# MotorCell_noPow.net
KiCad netlist of a schematic drawn in Altium Designer
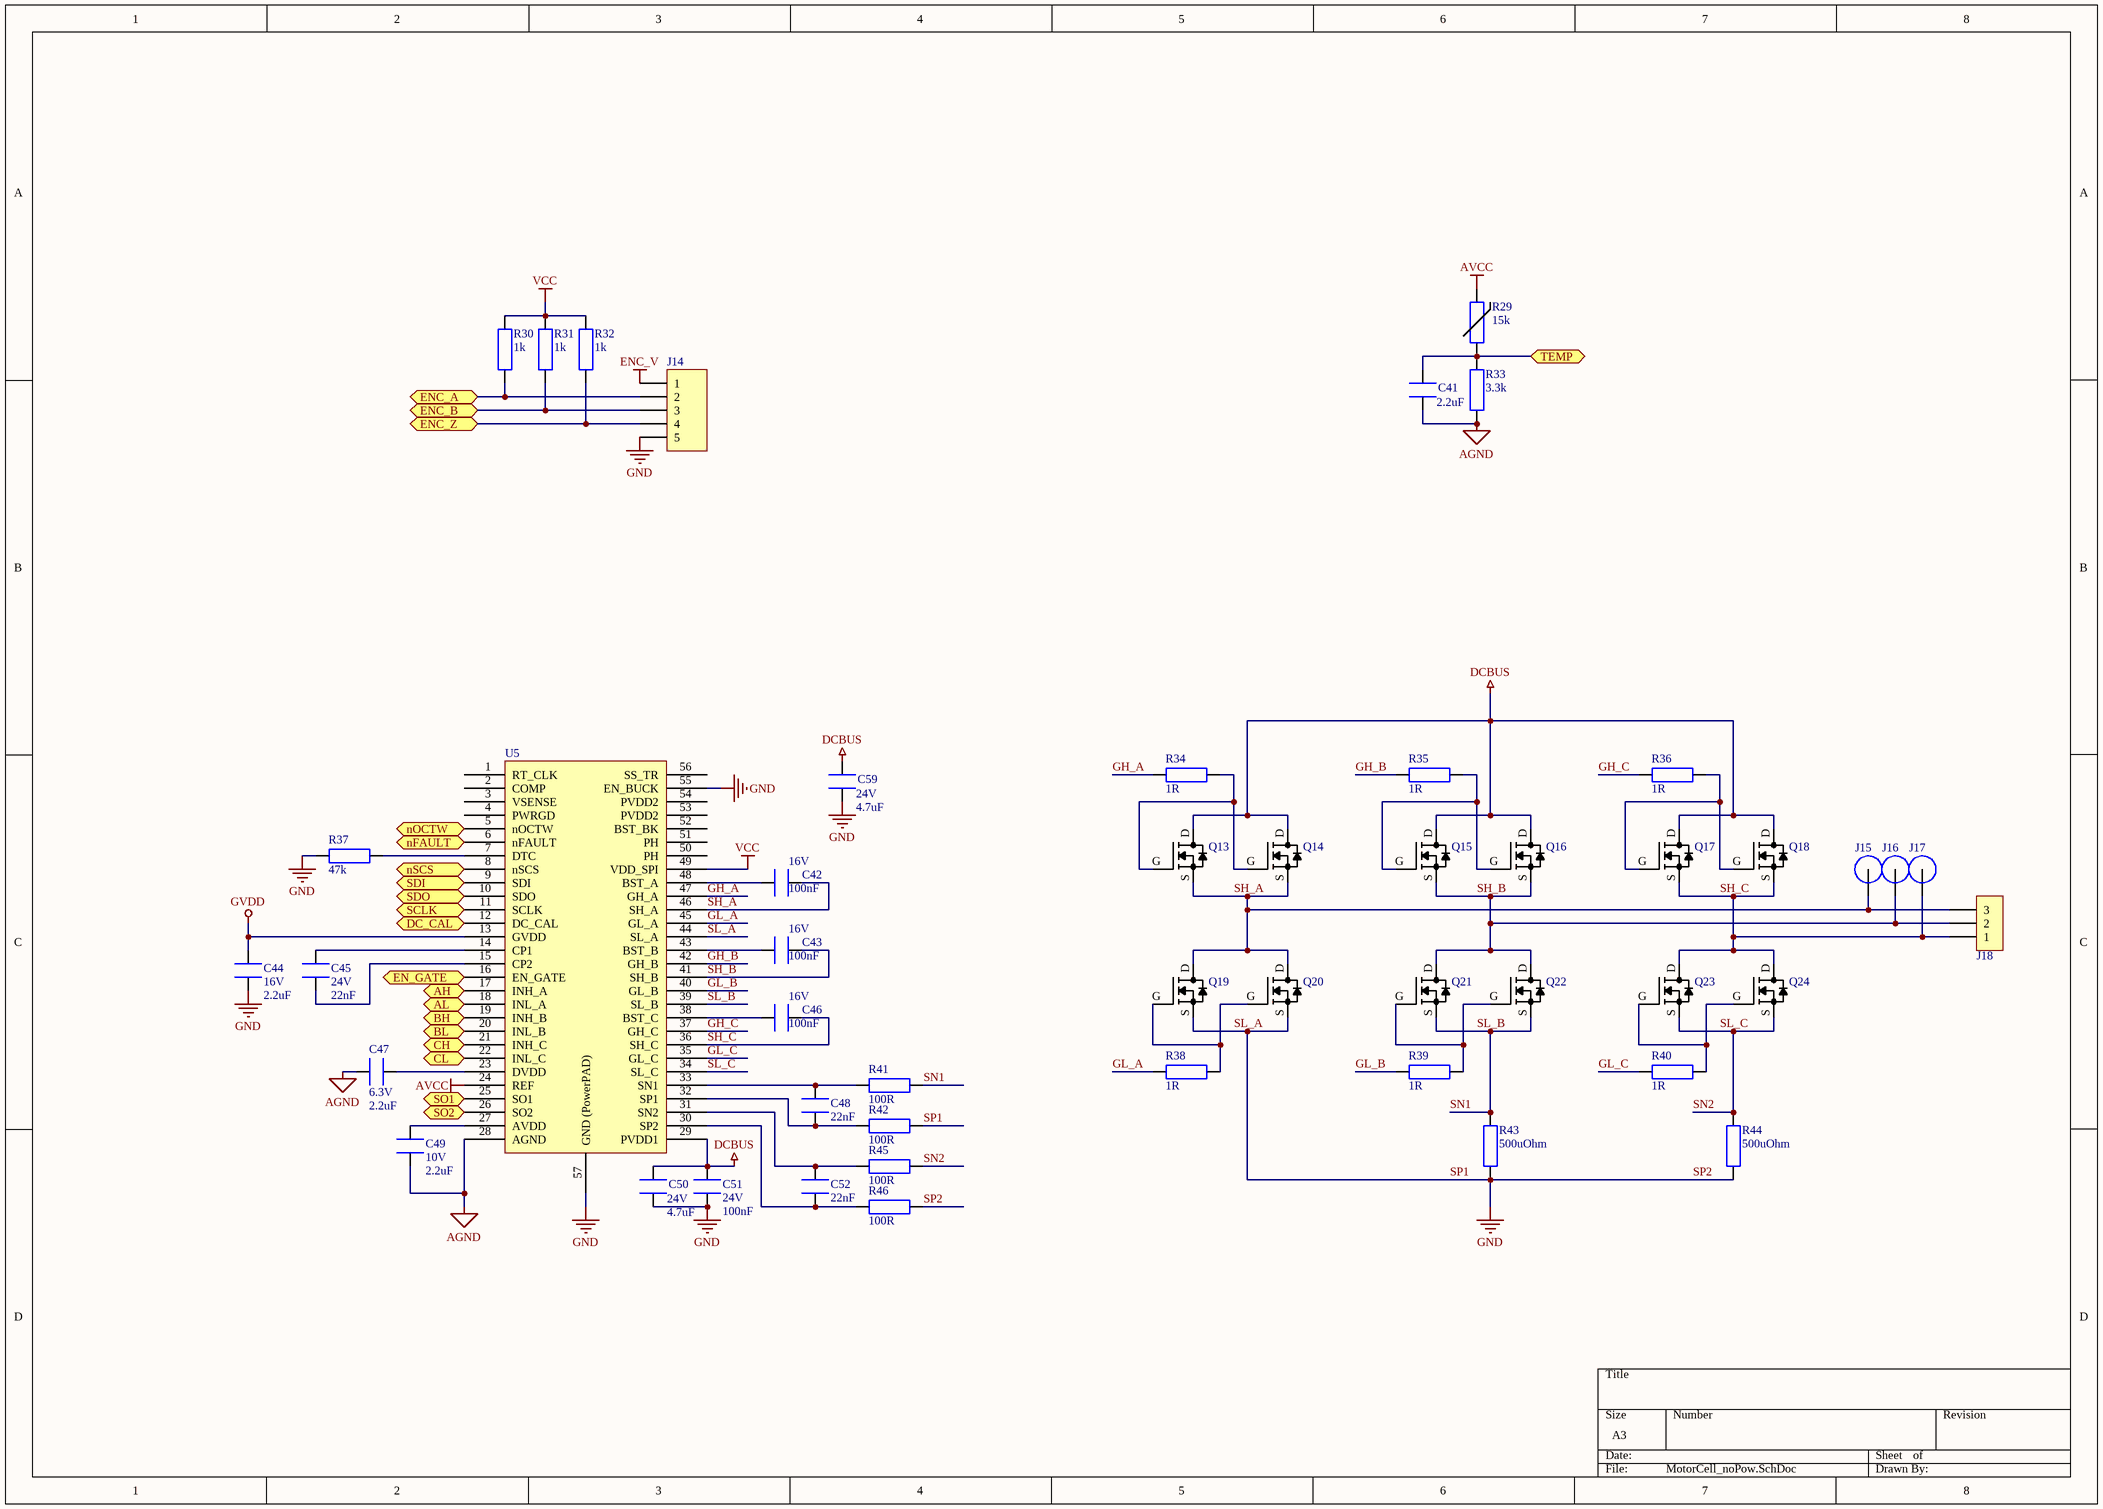
[diagram p0: MotorCell_noPow.SchDoc]

(export (version "E")
  (design (tool "Eeschema 10.0.6"))
  (components
    (comp (ref "C41")
      (value "2.2uF")
      (footprint "1608[0603]")
      (description "CAP General 0603")
      (libsource (lib "CustomComponents") (part "CAP_0603"))
    )
    (comp (ref "C42")
      (value "16V")
      (footprint "1608[0603]")
      (description "CAP General 0603")
      (fields (field (name "ALTIUM_VALUE") "100nF"))
      (libsource (lib "CustomComponents") (part "CAP_0603"))
    )
    (comp (ref "C43")
      (value "16V")
      (footprint "1608[0603]")
      (description "CAP General 0603")
      (fields (field (name "ALTIUM_VALUE") "100nF"))
      (libsource (lib "CustomComponents") (part "CAP_0603"))
    )
    (comp (ref "C44")
      (value "16V")
      (footprint "1608[0603]")
      (description "CAP General 0603")
      (fields (field (name "ALTIUM_VALUE") "2.2uF"))
      (libsource (lib "CustomComponents") (part "CAP_0603"))
    )
    (comp (ref "C45")
      (value "24V")
      (footprint "1608[0603]")
      (description "CAP General 0603")
      (fields (field (name "ALTIUM_VALUE") "22nF"))
      (libsource (lib "CustomComponents") (part "CAP_0603"))
    )
    (comp (ref "C46")
      (value "16V")
      (footprint "1608[0603]")
      (description "CAP General 0603")
      (fields (field (name "ALTIUM_VALUE") "100nF"))
      (libsource (lib "CustomComponents") (part "CAP_0603"))
    )
    (comp (ref "C47")
      (value "6.3V")
      (footprint "1608[0603]")
      (description "CAP General 0603")
      (fields (field (name "ALTIUM_VALUE") "2.2uF"))
      (libsource (lib "CustomComponents") (part "CAP_0603"))
    )
    (comp (ref "C48")
      (value "22nF")
      (footprint "1608[0603]")
      (description "CAP General 0603")
      (libsource (lib "CustomComponents") (part "CAP_0603"))
    )
    (comp (ref "C49")
      (value "10V")
      (footprint "1608[0603]")
      (description "CAP General 0603")
      (fields (field (name "ALTIUM_VALUE") "2.2uF"))
      (libsource (lib "CustomComponents") (part "CAP_0603"))
    )
    (comp (ref "C50")
      (value "24V")
      (footprint "CAPC2012X09N")
      (description "CAP CER 4.7UF 35V X5R 0805")
      (fields (field (name "ALTIUM_VALUE") "4.7uF"))
      (libsource (lib "CustomComponents") (part "GRM219R6YA475KA73D"))
    )
    (comp (ref "C51")
      (value "24V")
      (footprint "1608[0603]")
      (description "CAP General 0603")
      (fields (field (name "ALTIUM_VALUE") "100nF"))
      (libsource (lib "CustomComponents") (part "CAP_0603"))
    )
    (comp (ref "C52")
      (value "22nF")
      (footprint "1608[0603]")
      (description "CAP General 0603")
      (libsource (lib "CustomComponents") (part "CAP_0603"))
    )
    (comp (ref "C59")
      (value "24V")
      (footprint "CAPC2012X09N")
      (description "CAP CER 4.7UF 35V X5R 0805")
      (fields (field (name "ALTIUM_VALUE") "4.7uF"))
      (libsource (lib "CustomComponents") (part "GRM219R6YA475KA73D"))
    )
    (comp (ref "J14")
      (value "~")
      (footprint "HDR1X5")
      (description "Header, 5-Pin")
      (fields (field (name "PUBLISHER") "Altium Limited"))
      (libsource (lib "Miscellaneous Connectors") (part "Header 5"))
    )
    (comp (ref "J15")
      (value "~")
      (footprint "M3 Spade Hole")
      (description "M3 Spade Terminal")
      (libsource (lib "CustomComponents") (part "M3 Spade Terminal"))
    )
    (comp (ref "J16")
      (value "~")
      (footprint "M3 Spade Hole")
      (description "M3 Spade Terminal")
      (libsource (lib "CustomComponents") (part "M3 Spade Terminal"))
    )
    (comp (ref "J17")
      (value "~")
      (footprint "M3 Spade Hole")
      (description "M3 Spade Terminal")
      (libsource (lib "CustomComponents") (part "M3 Spade Terminal"))
    )
    (comp (ref "J18")
      (value "~")
      (footprint "MC000051")
      (description "TERMINAL BLOCK, WIRE TO BRD, 3POS, 10AWG")
      (libsource (lib "CustomComponents") (part "MC000051"))
    )
    (comp (ref "Q13")
      (value "~")
      (footprint "SO8FL")
      (description "MOSFET, N CH, 30V, 70A, SO-8 FL")
      (libsource (lib "CustomComponents") (part "NTMFS4937NT1G"))
    )
    (comp (ref "Q14")
      (value "~")
      (footprint "SO8FL_FILL")
      (description "MOSFET, N CH, 30V, 70A, SO-8 FL")
      (libsource (lib "CustomComponents") (part "NTMFS4937NT1G"))
    )
    (comp (ref "Q15")
      (value "~")
      (footprint "SO8FL")
      (description "MOSFET, N CH, 30V, 70A, SO-8 FL")
      (libsource (lib "CustomComponents") (part "NTMFS4937NT1G"))
    )
    (comp (ref "Q16")
      (value "~")
      (footprint "SO8FL_FILL")
      (description "MOSFET, N CH, 30V, 70A, SO-8 FL")
      (libsource (lib "CustomComponents") (part "NTMFS4937NT1G"))
    )
    (comp (ref "Q17")
      (value "~")
      (footprint "SO8FL")
      (description "MOSFET, N CH, 30V, 70A, SO-8 FL")
      (libsource (lib "CustomComponents") (part "NTMFS4937NT1G"))
    )
    (comp (ref "Q18")
      (value "~")
      (footprint "SO8FL_FILL")
      (description "MOSFET, N CH, 30V, 70A, SO-8 FL")
      (libsource (lib "CustomComponents") (part "NTMFS4937NT1G"))
    )
    (comp (ref "Q19")
      (value "~")
      (footprint "SO8FL")
      (description "MOSFET, N CH, 30V, 70A, SO-8 FL")
      (libsource (lib "CustomComponents") (part "NTMFS4937NT1G"))
    )
    (comp (ref "Q20")
      (value "~")
      (footprint "SO8FL")
      (description "MOSFET, N CH, 30V, 70A, SO-8 FL")
      (libsource (lib "CustomComponents") (part "NTMFS4937NT1G"))
    )
    (comp (ref "Q21")
      (value "~")
      (footprint "SO8FL")
      (description "MOSFET, N CH, 30V, 70A, SO-8 FL")
      (libsource (lib "CustomComponents") (part "NTMFS4937NT1G"))
    )
    (comp (ref "Q22")
      (value "~")
      (footprint "SO8FL")
      (description "MOSFET, N CH, 30V, 70A, SO-8 FL")
      (libsource (lib "CustomComponents") (part "NTMFS4937NT1G"))
    )
    (comp (ref "Q23")
      (value "~")
      (footprint "SO8FL")
      (description "MOSFET, N CH, 30V, 70A, SO-8 FL")
      (libsource (lib "CustomComponents") (part "NTMFS4937NT1G"))
    )
    (comp (ref "Q24")
      (value "~")
      (footprint "SO8FL")
      (description "MOSFET, N CH, 30V, 70A, SO-8 FL")
      (libsource (lib "CustomComponents") (part "NTMFS4937NT1G"))
    )
    (comp (ref "R29")
      (value "15k")
      (footprint "RESC1608X06L")
      (description "THERMISTOR, 15K, 5%, SMD, NTC")
      (libsource (lib "CustomComponents") (part "NTCS0603E3153JMT"))
    )
    (comp (ref "R30")
      (value "1k")
      (footprint "RESC1608X55N")
      (description "RES General 1% 0603")
      (libsource (lib "CustomComponents") (part "RES_0603"))
    )
    (comp (ref "R31")
      (value "1k")
      (footprint "RESC1608X55N")
      (description "RES General 1% 0603")
      (libsource (lib "CustomComponents") (part "RES_0603"))
    )
    (comp (ref "R32")
      (value "1k")
      (footprint "RESC1608X55N")
      (description "RES General 1% 0603")
      (libsource (lib "CustomComponents") (part "RES_0603"))
    )
    (comp (ref "R33")
      (value "3.3k")
      (footprint "RESC1608X55N")
      (description "RES General 1% 0603")
      (libsource (lib "CustomComponents") (part "RES_0603"))
    )
    (comp (ref "R34")
      (value "1R")
      (footprint "RESC1608X55N")
      (description "RES General 1% 0603")
      (libsource (lib "CustomComponents") (part "RES_0603"))
    )
    (comp (ref "R35")
      (value "1R")
      (footprint "RESC1608X55N")
      (description "RES General 1% 0603")
      (libsource (lib "CustomComponents") (part "RES_0603"))
    )
    (comp (ref "R36")
      (value "1R")
      (footprint "RESC1608X55N")
      (description "RES General 1% 0603")
      (libsource (lib "CustomComponents") (part "RES_0603"))
    )
    (comp (ref "R37")
      (value "47k")
      (footprint "RESC1608X55N")
      (description "RES General 1% 0603")
      (libsource (lib "CustomComponents") (part "RES_0603"))
    )
    (comp (ref "R38")
      (value "1R")
      (footprint "RESC1608X55N")
      (description "RES General 1% 0603")
      (libsource (lib "CustomComponents") (part "RES_0603"))
    )
    (comp (ref "R39")
      (value "1R")
      (footprint "RESC1608X55N")
      (description "RES General 1% 0603")
      (libsource (lib "CustomComponents") (part "RES_0603"))
    )
    (comp (ref "R40")
      (value "1R")
      (footprint "RESC1608X55N")
      (description "RES General 1% 0603")
      (libsource (lib "CustomComponents") (part "RES_0603"))
    )
    (comp (ref "R41")
      (value "100R")
      (footprint "RESC1608X55N")
      (description "RES General 1% 0603")
      (libsource (lib "CustomComponents") (part "RES_0603"))
    )
    (comp (ref "R42")
      (value "100R")
      (footprint "RESC1608X55N")
      (description "RES General 1% 0603")
      (libsource (lib "CustomComponents") (part "RES_0603"))
    )
    (comp (ref "R43")
      (value "500uOhm")
      (footprint "RESC6432X09N")
      (description "RES SMD 0.0005 OHM 1% 3W 2512")
      (libsource (lib "CustomComponents") (part "CSR2512C0R0005F"))
    )
    (comp (ref "R44")
      (value "500uOhm")
      (footprint "RESC6432X09N")
      (description "RES SMD 0.0005 OHM 1% 3W 2512")
      (libsource (lib "CustomComponents") (part "CSR2512C0R0005F"))
    )
    (comp (ref "R45")
      (value "100R")
      (footprint "RESC1608X55N")
      (description "RES General 1% 0603")
      (libsource (lib "CustomComponents") (part "RES_0603"))
    )
    (comp (ref "R46")
      (value "100R")
      (footprint "RESC1608X55N")
      (description "RES General 1% 0603")
      (libsource (lib "CustomComponents") (part "RES_0603"))
    )
    (comp (ref "U5")
      (value "~")
      (footprint "TSSOP50P810X120_HS-57N")
      (description "MOTOR DRIVER, 3PH, 56HTSSOP")
      (libsource (lib "CustomComponents") (part "DRV8301"))
    )
  )
  (nets
    (net (code "1") (name "/AH") (class "Default")
      (node (ref "U5") (pin "17") (pinfunction "INH_A_17") (pintype "passive"))
    )
    (net (code "2") (name "/AL") (class "Default")
      (node (ref "U5") (pin "18") (pinfunction "INL_A_18") (pintype "passive"))
    )
    (net (code "3") (name "/BH") (class "Default")
      (node (ref "U5") (pin "19") (pinfunction "INH_B_19") (pintype "passive"))
    )
    (net (code "4") (name "/BL") (class "Default")
      (node (ref "U5") (pin "20") (pinfunction "INL_B_20") (pintype "passive"))
    )
    (net (code "5") (name "/CH") (class "Default")
      (node (ref "U5") (pin "21") (pinfunction "INH_C_21") (pintype "passive"))
    )
    (net (code "6") (name "/CL") (class "Default")
      (node (ref "U5") (pin "22") (pinfunction "INL_C_22") (pintype "passive"))
    )
    (net (code "7") (name "/DC_CAL") (class "Default")
      (node (ref "U5") (pin "12") (pinfunction "DC_CAL_12") (pintype "passive"))
    )
    (net (code "8") (name "/ENC_A") (class "Default")
      (node (ref "J14") (pin "2") (pinfunction "2_2") (pintype "passive"))
      (node (ref "R30") (pin "2") (pinfunction "0_2") (pintype "passive"))
    )
    (net (code "9") (name "/ENC_B") (class "Default")
      (node (ref "J14") (pin "3") (pinfunction "3_3") (pintype "passive"))
      (node (ref "R31") (pin "2") (pinfunction "0_2") (pintype "passive"))
    )
    (net (code "10") (name "/ENC_Z") (class "Default")
      (node (ref "J14") (pin "4") (pinfunction "4_4") (pintype "passive"))
      (node (ref "R32") (pin "2") (pinfunction "0_2") (pintype "passive"))
    )
    (net (code "11") (name "/EN_GATE") (class "Default")
      (node (ref "U5") (pin "16") (pinfunction "EN_GATE_16") (pintype "passive"))
    )
    (net (code "12") (name "/GH_A") (class "Default")
      (node (ref "R34") (pin "1") (pinfunction "0_1") (pintype "passive"))
      (node (ref "U5") (pin "47") (pinfunction "GH_A_47") (pintype "passive"))
    )
    (net (code "13") (name "/GH_B") (class "Default")
      (node (ref "R35") (pin "1") (pinfunction "0_1") (pintype "passive"))
      (node (ref "U5") (pin "42") (pinfunction "GH_B_42") (pintype "passive"))
    )
    (net (code "14") (name "/GH_C") (class "Default")
      (node (ref "R36") (pin "1") (pinfunction "0_1") (pintype "passive"))
      (node (ref "U5") (pin "37") (pinfunction "GH_C_37") (pintype "passive"))
    )
    (net (code "15") (name "/GL_A") (class "Default")
      (node (ref "R38") (pin "1") (pinfunction "0_1") (pintype "passive"))
      (node (ref "U5") (pin "45") (pinfunction "GL_A_45") (pintype "passive"))
    )
    (net (code "16") (name "/GL_B") (class "Default")
      (node (ref "R39") (pin "1") (pinfunction "0_1") (pintype "passive"))
      (node (ref "U5") (pin "40") (pinfunction "GL_B_40") (pintype "passive"))
    )
    (net (code "17") (name "/GL_C") (class "Default")
      (node (ref "R40") (pin "1") (pinfunction "0_1") (pintype "passive"))
      (node (ref "U5") (pin "35") (pinfunction "GL_C_35") (pintype "passive"))
    )
    (net (code "18") (name "/SCLK") (class "Default")
      (node (ref "U5") (pin "11") (pinfunction "SCLK_11") (pintype "passive"))
    )
    (net (code "19") (name "/SDI") (class "Default")
      (node (ref "U5") (pin "9") (pinfunction "SDI_9") (pintype "passive"))
    )
    (net (code "20") (name "/SDO") (class "Default")
      (node (ref "U5") (pin "10") (pinfunction "SDO_10") (pintype "passive"))
    )
    (net (code "21") (name "/SH_A") (class "Default")
      (node (ref "C42") (pin "1") (pinfunction "1_1") (pintype "passive"))
      (node (ref "J15") (pin "1") (pinfunction "1_1") (pintype "passive"))
      (node (ref "J18") (pin "3") (pinfunction "3_3") (pintype "passive"))
      (node (ref "Q13") (pin "S") (pinfunction "S_S") (pintype "passive"))
      (node (ref "Q14") (pin "S") (pinfunction "S_S") (pintype "passive"))
      (node (ref "Q19") (pin "D") (pinfunction "D_D") (pintype "passive"))
      (node (ref "Q20") (pin "D") (pinfunction "D_D") (pintype "passive"))
      (node (ref "U5") (pin "46") (pinfunction "SH_A_46") (pintype "passive"))
    )
    (net (code "22") (name "/SH_B") (class "Default")
      (node (ref "C43") (pin "1") (pinfunction "1_1") (pintype "passive"))
      (node (ref "J16") (pin "1") (pinfunction "1_1") (pintype "passive"))
      (node (ref "J18") (pin "2") (pinfunction "2_2") (pintype "passive"))
      (node (ref "Q15") (pin "S") (pinfunction "S_S") (pintype "passive"))
      (node (ref "Q16") (pin "S") (pinfunction "S_S") (pintype "passive"))
      (node (ref "Q21") (pin "D") (pinfunction "D_D") (pintype "passive"))
      (node (ref "Q22") (pin "D") (pinfunction "D_D") (pintype "passive"))
      (node (ref "U5") (pin "41") (pinfunction "SH_B_41") (pintype "passive"))
    )
    (net (code "23") (name "/SH_C") (class "Default")
      (node (ref "C46") (pin "1") (pinfunction "1_1") (pintype "passive"))
      (node (ref "J17") (pin "1") (pinfunction "1_1") (pintype "passive"))
      (node (ref "J18") (pin "1") (pinfunction "1_1") (pintype "passive"))
      (node (ref "Q17") (pin "S") (pinfunction "S_S") (pintype "passive"))
      (node (ref "Q18") (pin "S") (pinfunction "S_S") (pintype "passive"))
      (node (ref "Q23") (pin "D") (pinfunction "D_D") (pintype "passive"))
      (node (ref "Q24") (pin "D") (pinfunction "D_D") (pintype "passive"))
      (node (ref "U5") (pin "36") (pinfunction "SH_C_36") (pintype "passive"))
    )
    (net (code "24") (name "/SL_B") (class "Default")
      (node (ref "Q21") (pin "S") (pinfunction "S_S") (pintype "passive"))
      (node (ref "Q22") (pin "S") (pinfunction "S_S") (pintype "passive"))
      (node (ref "R41") (pin "1") (pinfunction "0_1") (pintype "passive"))
      (node (ref "R43") (pin "2") (pinfunction "0_2") (pintype "passive"))
      (node (ref "U5") (pin "39") (pinfunction "SL_B_39") (pintype "passive"))
    )
    (net (code "25") (name "/SL_C") (class "Default")
      (node (ref "Q23") (pin "S") (pinfunction "S_S") (pintype "passive"))
      (node (ref "Q24") (pin "S") (pinfunction "S_S") (pintype "passive"))
      (node (ref "R44") (pin "2") (pinfunction "0_2") (pintype "passive"))
      (node (ref "R45") (pin "1") (pinfunction "0_1") (pintype "passive"))
      (node (ref "U5") (pin "34") (pinfunction "SL_C_34") (pintype "passive"))
    )
    (net (code "26") (name "/SO1") (class "Default")
      (node (ref "U5") (pin "25") (pinfunction "SO1_25") (pintype "passive"))
    )
    (net (code "27") (name "/SO2") (class "Default")
      (node (ref "U5") (pin "26") (pinfunction "SO2_26") (pintype "passive"))
    )
    (net (code "28") (name "/TEMP") (class "Default")
      (node (ref "C41") (pin "2") (pinfunction "2_2") (pintype "passive"))
      (node (ref "R29") (pin "1") (pinfunction "0_1") (pintype "passive"))
      (node (ref "R33") (pin "1") (pinfunction "0_1") (pintype "passive"))
    )
    (net (code "29") (name "/nFAULT") (class "Default")
      (node (ref "U5") (pin "6") (pinfunction "nFAULT_6") (pintype "passive"))
    )
    (net (code "30") (name "/nOCTW") (class "Default")
      (node (ref "U5") (pin "5") (pinfunction "nOCTW_5") (pintype "passive"))
    )
    (net (code "31") (name "/nSCS") (class "Default")
      (node (ref "U5") (pin "8") (pinfunction "nSCS_8") (pintype "passive"))
    )
    (net (code "32") (name "AGND") (class "Default")
      (node (ref "C41") (pin "1") (pinfunction "1_1") (pintype "passive"))
      (node (ref "C47") (pin "1") (pinfunction "1_1") (pintype "passive"))
      (node (ref "C49") (pin "1") (pinfunction "1_1") (pintype "passive"))
      (node (ref "R33") (pin "2") (pinfunction "0_2") (pintype "passive"))
      (node (ref "U5") (pin "28") (pinfunction "AGND_28") (pintype "passive"))
    )
    (net (code "33") (name "AVCC") (class "Default")
      (node (ref "R29") (pin "2") (pinfunction "0_2") (pintype "passive"))
      (node (ref "U5") (pin "24") (pinfunction "REF_24") (pintype "passive"))
    )
    (net (code "34") (name "DCBUS") (class "Default")
      (node (ref "C50") (pin "2") (pinfunction "2_2") (pintype "passive"))
      (node (ref "C51") (pin "1") (pinfunction "1_1") (pintype "passive"))
      (node (ref "C59") (pin "2") (pinfunction "2_2") (pintype "passive"))
      (node (ref "Q13") (pin "D") (pinfunction "D_D") (pintype "passive"))
      (node (ref "Q14") (pin "D") (pinfunction "D_D") (pintype "passive"))
      (node (ref "Q15") (pin "D") (pinfunction "D_D") (pintype "passive"))
      (node (ref "Q16") (pin "D") (pinfunction "D_D") (pintype "passive"))
      (node (ref "Q17") (pin "D") (pinfunction "D_D") (pintype "passive"))
      (node (ref "Q18") (pin "D") (pinfunction "D_D") (pintype "passive"))
      (node (ref "U5") (pin "29") (pinfunction "PVDD1_29") (pintype "passive"))
    )
    (net (code "35") (name "ENC_V") (class "Default")
      (node (ref "J14") (pin "1") (pinfunction "1_1") (pintype "passive"))
    )
    (net (code "36") (name "GND") (class "Default")
      (node (ref "C44") (pin "1") (pinfunction "1_1") (pintype "passive"))
      (node (ref "C50") (pin "1") (pinfunction "1_1") (pintype "passive"))
      (node (ref "C51") (pin "2") (pinfunction "2_2") (pintype "passive"))
      (node (ref "C59") (pin "1") (pinfunction "1_1") (pintype "passive"))
      (node (ref "J14") (pin "5") (pinfunction "5_5") (pintype "passive"))
      (node (ref "Q19") (pin "S") (pinfunction "S_S") (pintype "passive"))
      (node (ref "Q20") (pin "S") (pinfunction "S_S") (pintype "passive"))
      (node (ref "R37") (pin "2") (pinfunction "0_2") (pintype "passive"))
      (node (ref "R42") (pin "1") (pinfunction "0_1") (pintype "passive"))
      (node (ref "R43") (pin "1") (pinfunction "0_1") (pintype "passive"))
      (node (ref "R44") (pin "1") (pinfunction "0_1") (pintype "passive"))
      (node (ref "R46") (pin "1") (pinfunction "0_1") (pintype "passive"))
      (node (ref "U5") (pin "44") (pinfunction "SL_A_44") (pintype "passive"))
      (node (ref "U5") (pin "55") (pinfunction "EN_BUCK_55") (pintype "passive"))
      (node (ref "U5") (pin "57") (pinfunction "GND_(PowerPAD)_57") (pintype "passive"))
    )
    (net (code "37") (name "GVDD") (class "Default")
      (node (ref "C44") (pin "2") (pinfunction "2_2") (pintype "passive"))
      (node (ref "U5") (pin "13") (pinfunction "GVDD_13") (pintype "passive"))
    )
    (net (code "38") (name "Net-(Q13-PadG)") (class "Default")
      (node (ref "Q13") (pin "G") (pinfunction "G_G") (pintype "passive"))
      (node (ref "Q14") (pin "G") (pinfunction "G_G") (pintype "passive"))
      (node (ref "R34") (pin "2") (pinfunction "0_2") (pintype "passive"))
    )
    (net (code "39") (name "Net-(Q15-PadG)") (class "Default")
      (node (ref "Q15") (pin "G") (pinfunction "G_G") (pintype "passive"))
      (node (ref "Q16") (pin "G") (pinfunction "G_G") (pintype "passive"))
      (node (ref "R35") (pin "2") (pinfunction "0_2") (pintype "passive"))
    )
    (net (code "40") (name "Net-(Q17-PadG)") (class "Default")
      (node (ref "Q17") (pin "G") (pinfunction "G_G") (pintype "passive"))
      (node (ref "Q18") (pin "G") (pinfunction "G_G") (pintype "passive"))
      (node (ref "R36") (pin "2") (pinfunction "0_2") (pintype "passive"))
    )
    (net (code "41") (name "Net-(Q19-PadG)") (class "Default")
      (node (ref "Q19") (pin "G") (pinfunction "G_G") (pintype "passive"))
      (node (ref "Q20") (pin "G") (pinfunction "G_G") (pintype "passive"))
      (node (ref "R38") (pin "2") (pinfunction "0_2") (pintype "passive"))
    )
    (net (code "42") (name "Net-(Q21-PadG)") (class "Default")
      (node (ref "Q21") (pin "G") (pinfunction "G_G") (pintype "passive"))
      (node (ref "Q22") (pin "G") (pinfunction "G_G") (pintype "passive"))
      (node (ref "R39") (pin "2") (pinfunction "0_2") (pintype "passive"))
    )
    (net (code "43") (name "Net-(Q23-PadG)") (class "Default")
      (node (ref "Q23") (pin "G") (pinfunction "G_G") (pintype "passive"))
      (node (ref "Q24") (pin "G") (pinfunction "G_G") (pintype "passive"))
      (node (ref "R40") (pin "2") (pinfunction "0_2") (pintype "passive"))
    )
    (net (code "44") (name "Net-(U5-AVDD)") (class "Default")
      (node (ref "C49") (pin "2") (pinfunction "2_2") (pintype "passive"))
      (node (ref "U5") (pin "27") (pinfunction "AVDD_27") (pintype "passive"))
    )
    (net (code "45") (name "Net-(U5-BST_A)") (class "Default")
      (node (ref "C42") (pin "2") (pinfunction "2_2") (pintype "passive"))
      (node (ref "U5") (pin "48") (pinfunction "BST_A_48") (pintype "passive"))
    )
    (net (code "46") (name "Net-(U5-BST_B)") (class "Default")
      (node (ref "C43") (pin "2") (pinfunction "2_2") (pintype "passive"))
      (node (ref "U5") (pin "43") (pinfunction "BST_B_43") (pintype "passive"))
    )
    (net (code "47") (name "Net-(U5-BST_C)") (class "Default")
      (node (ref "C46") (pin "2") (pinfunction "2_2") (pintype "passive"))
      (node (ref "U5") (pin "38") (pinfunction "BST_C_38") (pintype "passive"))
    )
    (net (code "48") (name "Net-(U5-CP1)") (class "Default")
      (node (ref "C45") (pin "1") (pinfunction "1_1") (pintype "passive"))
      (node (ref "U5") (pin "14") (pinfunction "CP1_14") (pintype "passive"))
    )
    (net (code "49") (name "Net-(U5-CP2)") (class "Default")
      (node (ref "C45") (pin "2") (pinfunction "2_2") (pintype "passive"))
      (node (ref "U5") (pin "15") (pinfunction "CP2_15") (pintype "passive"))
    )
    (net (code "50") (name "Net-(U5-DTC)") (class "Default")
      (node (ref "R37") (pin "1") (pinfunction "0_1") (pintype "passive"))
      (node (ref "U5") (pin "7") (pinfunction "DTC_7") (pintype "passive"))
    )
    (net (code "51") (name "Net-(U5-DVDD)") (class "Default")
      (node (ref "C47") (pin "2") (pinfunction "2_2") (pintype "passive"))
      (node (ref "U5") (pin "23") (pinfunction "DVDD_23") (pintype "passive"))
    )
    (net (code "52") (name "Net-(U5-SN1)") (class "Default")
      (node (ref "C48") (pin "1") (pinfunction "1_1") (pintype "passive"))
      (node (ref "R41") (pin "2") (pinfunction "0_2") (pintype "passive"))
      (node (ref "U5") (pin "33") (pinfunction "SN1_33") (pintype "passive"))
    )
    (net (code "53") (name "Net-(U5-SN2)") (class "Default")
      (node (ref "C52") (pin "1") (pinfunction "1_1") (pintype "passive"))
      (node (ref "R45") (pin "2") (pinfunction "0_2") (pintype "passive"))
      (node (ref "U5") (pin "31") (pinfunction "SN2_31") (pintype "passive"))
    )
    (net (code "54") (name "Net-(U5-SP1)") (class "Default")
      (node (ref "C48") (pin "2") (pinfunction "2_2") (pintype "passive"))
      (node (ref "R42") (pin "2") (pinfunction "0_2") (pintype "passive"))
      (node (ref "U5") (pin "32") (pinfunction "SP1_32") (pintype "passive"))
    )
    (net (code "55") (name "Net-(U5-SP2)") (class "Default")
      (node (ref "C52") (pin "2") (pinfunction "2_2") (pintype "passive"))
      (node (ref "R46") (pin "2") (pinfunction "0_2") (pintype "passive"))
      (node (ref "U5") (pin "30") (pinfunction "SP2_30") (pintype "passive"))
    )
    (net (code "56") (name "VCC") (class "Default")
      (node (ref "R30") (pin "1") (pinfunction "0_1") (pintype "passive"))
      (node (ref "R31") (pin "1") (pinfunction "0_1") (pintype "passive"))
      (node (ref "R32") (pin "1") (pinfunction "0_1") (pintype "passive"))
      (node (ref "U5") (pin "49") (pinfunction "VDD_SPI_49") (pintype "passive"))
    )
    (net (code "57") (name "unconnected-(U5-BST_BK-Pad52)") (class "Default")
      (node (ref "U5") (pin "52") (pinfunction "BST_BK_52") (pintype "passive"))
    )
    (net (code "58") (name "unconnected-(U5-COMP-Pad2)") (class "Default")
      (node (ref "U5") (pin "2") (pinfunction "COMP_2") (pintype "passive"))
    )
    (net (code "59") (name "unconnected-(U5-PH-Pad50)") (class "Default")
      (node (ref "U5") (pin "50") (pinfunction "PH_50") (pintype "passive"))
    )
    (net (code "60") (name "unconnected-(U5-PH-Pad51)") (class "Default")
      (node (ref "U5") (pin "51") (pinfunction "PH_51") (pintype "passive"))
    )
    (net (code "61") (name "unconnected-(U5-PVDD2-Pad53)") (class "Default")
      (node (ref "U5") (pin "53") (pinfunction "PVDD2_53") (pintype "passive"))
    )
    (net (code "62") (name "unconnected-(U5-PVDD2-Pad54)") (class "Default")
      (node (ref "U5") (pin "54") (pinfunction "PVDD2_54") (pintype "passive"))
    )
    (net (code "63") (name "unconnected-(U5-PWRGD-Pad4)") (class "Default")
      (node (ref "U5") (pin "4") (pinfunction "PWRGD_4") (pintype "passive"))
    )
    (net (code "64") (name "unconnected-(U5-RT_CLK-Pad1)") (class "Default")
      (node (ref "U5") (pin "1") (pinfunction "RT_CLK_1") (pintype "passive"))
    )
    (net (code "65") (name "unconnected-(U5-SS_TR-Pad56)") (class "Default")
      (node (ref "U5") (pin "56") (pinfunction "SS_TR_56") (pintype "passive"))
    )
    (net (code "66") (name "unconnected-(U5-VSENSE-Pad3)") (class "Default")
      (node (ref "U5") (pin "3") (pinfunction "VSENSE_3") (pintype "passive"))
    )
  )
)
